# Serial.net
KiCad netlist of a schematic drawn in Altium Designer
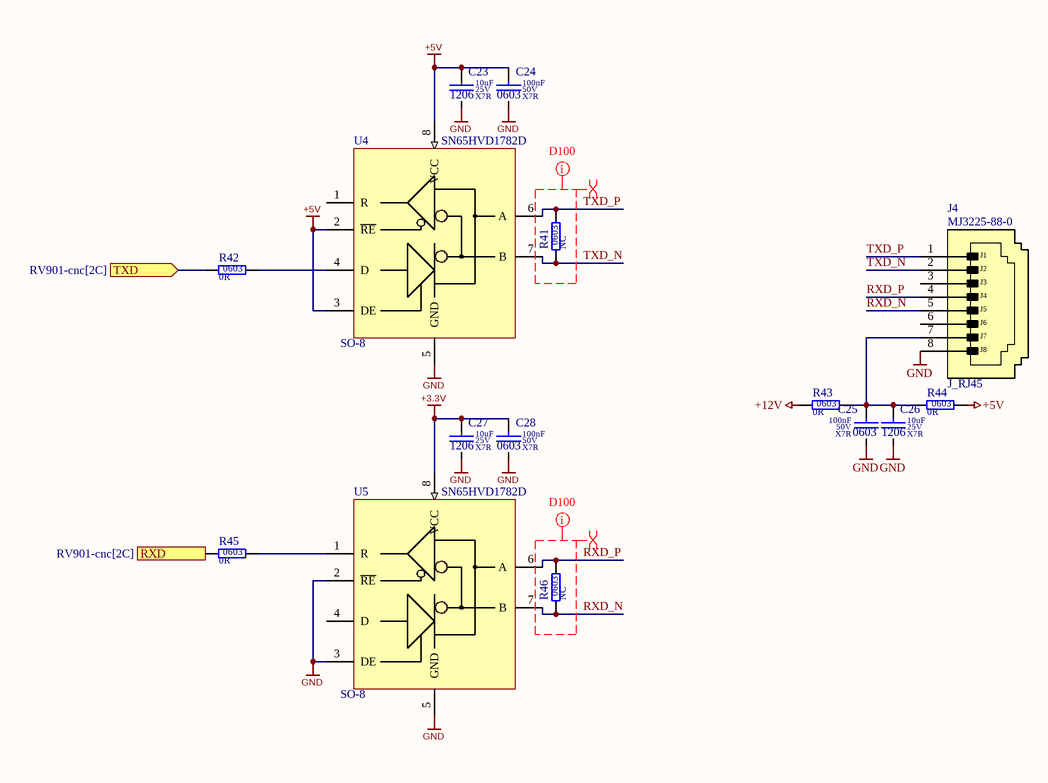
[diagram p0: Serial.SchDoc]

(export (version "E")
  (design (tool "Eeschema 10.0.6"))
  (components
    (comp (ref "C23")
      (value "10uF")
      (footprint "C_1206_3216")
      (description "Capacitor")
      (fields
        (field (name "DIELECTRIC") "X7R")
        (field (name "VOLTAGE") "25V")
        (field (name "SCH_FOOTPRINT") "1206")
        (field (name "PART NUMBER") "C_10uF_25V_X7R_1206_10")
        (field (name "MANUFACTURER") "Samsung")
      )
      (libsource (lib "Library") (part "C"))
    )
    (comp (ref "C24")
      (value "100nF")
      (footprint "C_0603_1608")
      (description "Capacitor")
      (fields
        (field (name "DIELECTRIC") "X7R")
        (field (name "VOLTAGE") "50V")
        (field (name "SCH_FOOTPRINT") "0603")
        (field (name "PART NUMBER") "C_100nF_50V_X7R_0603_5")
        (field (name "MANUFACTURER") "Samsung")
      )
      (libsource (lib "Library") (part "C"))
    )
    (comp (ref "C25")
      (value "100nF")
      (footprint "C_0603_1608")
      (description "Capacitor")
      (fields
        (field (name "DIELECTRIC") "X7R")
        (field (name "VOLTAGE") "50V")
        (field (name "SCH_FOOTPRINT") "0603")
        (field (name "PART NUMBER") "C_100nF_50V_X7R_0603_5")
        (field (name "MANUFACTURER") "Samsung")
      )
      (libsource (lib "Library") (part "C"))
    )
    (comp (ref "C26")
      (value "10uF")
      (footprint "C_1206_3216")
      (description "Capacitor")
      (fields
        (field (name "DIELECTRIC") "X7R")
        (field (name "VOLTAGE") "25V")
        (field (name "SCH_FOOTPRINT") "1206")
        (field (name "PART NUMBER") "C_10uF_25V_X7R_1206_10")
        (field (name "MANUFACTURER") "Samsung")
      )
      (libsource (lib "Library") (part "C"))
    )
    (comp (ref "C27")
      (value "10uF")
      (footprint "C_1206_3216")
      (description "Capacitor")
      (fields
        (field (name "DIELECTRIC") "X7R")
        (field (name "VOLTAGE") "25V")
        (field (name "SCH_FOOTPRINT") "1206")
        (field (name "PART NUMBER") "C_10uF_25V_X7R_1206_10")
        (field (name "MANUFACTURER") "Samsung")
      )
      (libsource (lib "Library") (part "C"))
    )
    (comp (ref "C28")
      (value "100nF")
      (footprint "C_0603_1608")
      (description "Capacitor")
      (fields
        (field (name "DIELECTRIC") "X7R")
        (field (name "VOLTAGE") "50V")
        (field (name "SCH_FOOTPRINT") "0603")
        (field (name "PART NUMBER") "C_100nF_50V_X7R_0603_5")
        (field (name "MANUFACTURER") "Samsung")
      )
      (libsource (lib "Library") (part "C"))
    )
    (comp (ref "J4")
      (value "MJ3225-88-0")
      (footprint "J_RJ45_MJ3225-88-0")
      (fields
        (field (name "SCH_FOOTPRINT") "J_RJ45")
        (field (name "PART NUMBER") "J_RJ45_MJ3225-88-0")
        (field (name "MANUFACTURER") "Global Connector Technology")
        (field (name "Comment") "Modular Connector, Modular Jack, 1 x 1 (Port), 8P8C, Cat3")
      )
      (libsource (lib "Library") (part "J_RJ45"))
    )
    (comp (ref "R41")
      (value "NC")
      (footprint "R_NC_0603_1608")
      (fields
        (field (name "SCH_FOOTPRINT") "0603")
        (field (name "PART NUMBER") "R_GENERIC_0603")
        (field (name "Comment") "Resistor")
      )
      (libsource (lib "Library") (part "R"))
    )
    (comp (ref "R42")
      (value "0R")
      (footprint "R_0603_1608")
      (fields
        (field (name "SCH_FOOTPRINT") "0603")
        (field (name "PART NUMBER") "R_0R_0603_1")
        (field (name "VOLTAGE") "75V")
        (field (name "POWER") "100mW")
      )
      (libsource (lib "Library") (part "R"))
    )
    (comp (ref "R43")
      (value "0R")
      (footprint "R_0603_1608")
      (fields
        (field (name "SCH_FOOTPRINT") "0603")
        (field (name "PART NUMBER") "R_0R_0603_1")
        (field (name "VOLTAGE") "75V")
        (field (name "POWER") "100mW")
      )
      (libsource (lib "Library") (part "R"))
    )
    (comp (ref "R44")
      (value "0R")
      (footprint "R_0603_1608")
      (fields
        (field (name "SCH_FOOTPRINT") "0603")
        (field (name "PART NUMBER") "R_0R_0603_1")
        (field (name "VOLTAGE") "75V")
        (field (name "POWER") "100mW")
      )
      (libsource (lib "Library") (part "R"))
    )
    (comp (ref "R45")
      (value "0R")
      (footprint "R_0603_1608")
      (fields
        (field (name "SCH_FOOTPRINT") "0603")
        (field (name "PART NUMBER") "R_0R_0603_1")
        (field (name "VOLTAGE") "75V")
        (field (name "POWER") "100mW")
      )
      (libsource (lib "Library") (part "R"))
    )
    (comp (ref "R46")
      (value "NC")
      (footprint "R_NC_0603_1608")
      (fields
        (field (name "SCH_FOOTPRINT") "0603")
        (field (name "PART NUMBER") "R_GENERIC_0603")
        (field (name "Comment") "Resistor")
      )
      (libsource (lib "Library") (part "R"))
    )
    (comp (ref "U4")
      (value "SN65HVD1782D")
      (footprint "SOP8_SO8_SOIC8_4X5X18")
      (description "Fault-Protected  RS-485  Transceivers  With 3.3-V to 5-V Operation")
      (fields
        (field (name "SCH_FOOTPRINT") "SO-8")
        (field (name "PART NUMBER") "U_SN65HVD1782DR")
        (field (name "MANUFACTURER") "Texas Instruments")
      )
      (libsource (lib "Library") (part "U_RS485_HD_GENERIC"))
    )
    (comp (ref "U5")
      (value "SN65HVD1782D")
      (footprint "SOP8_SO8_SOIC8_4X5X18")
      (description "Fault-Protected  RS-485  Transceivers  With 3.3-V to 5-V Operation")
      (fields
        (field (name "SCH_FOOTPRINT") "SO-8")
        (field (name "PART NUMBER") "U_SN65HVD1782DR")
        (field (name "MANUFACTURER") "Texas Instruments")
      )
      (libsource (lib "Library") (part "U_RS485_HD_GENERIC"))
    )
  )
  (nets
    (net (code "1") (name "+3.3V") (class "Default")
      (node (ref "C27") (pin "1") (pinfunction "1_1") (pintype "passive"))
      (node (ref "C28") (pin "1") (pinfunction "1_1") (pintype "passive"))
      (node (ref "U5") (pin "8") (pinfunction "VCC_8") (pintype "input"))
    )
    (net (code "2") (name "+5V") (class "Default")
      (node (ref "C23") (pin "1") (pinfunction "1_1") (pintype "passive"))
      (node (ref "C24") (pin "1") (pinfunction "1_1") (pintype "passive"))
      (node (ref "R44") (pin "2") (pinfunction "2_2") (pintype "passive"))
      (node (ref "U4") (pin "2") (pinfunction "~{RE}_2") (pintype "passive"))
      (node (ref "U4") (pin "3") (pinfunction "DE_3") (pintype "passive"))
      (node (ref "U4") (pin "8") (pinfunction "VCC_8") (pintype "input"))
    )
    (net (code "3") (name "+12V") (class "Default")
      (node (ref "R43") (pin "1") (pinfunction "1_1") (pintype "passive"))
    )
    (net (code "4") (name "/RXD") (class "Default")
      (node (ref "R45") (pin "1") (pinfunction "1_1") (pintype "passive"))
    )
    (net (code "5") (name "/RXD_N") (class "Default")
      (node (ref "J4") (pin "5") (pintype "passive"))
      (node (ref "R46") (pin "1") (pinfunction "1_1") (pintype "passive"))
      (node (ref "U5") (pin "7") (pinfunction "B_7") (pintype "passive"))
    )
    (net (code "6") (name "/RXD_P") (class "Default")
      (node (ref "J4") (pin "4") (pintype "passive"))
      (node (ref "R46") (pin "2") (pinfunction "2_2") (pintype "passive"))
      (node (ref "U5") (pin "6") (pinfunction "A_6") (pintype "passive"))
    )
    (net (code "7") (name "/TXD") (class "Default")
      (node (ref "R42") (pin "1") (pinfunction "1_1") (pintype "passive"))
    )
    (net (code "8") (name "/TXD_N") (class "Default")
      (node (ref "J4") (pin "2") (pintype "passive"))
      (node (ref "R41") (pin "1") (pinfunction "1_1") (pintype "passive"))
      (node (ref "U4") (pin "7") (pinfunction "B_7") (pintype "passive"))
    )
    (net (code "9") (name "/TXD_P") (class "Default")
      (node (ref "J4") (pin "1") (pintype "passive"))
      (node (ref "R41") (pin "2") (pinfunction "2_2") (pintype "passive"))
      (node (ref "U4") (pin "6") (pinfunction "A_6") (pintype "passive"))
    )
    (net (code "10") (name "GND") (class "Default")
      (node (ref "C23") (pin "2") (pinfunction "2_2") (pintype "passive"))
      (node (ref "C24") (pin "2") (pinfunction "2_2") (pintype "passive"))
      (node (ref "C25") (pin "2") (pinfunction "2_2") (pintype "passive"))
      (node (ref "C26") (pin "2") (pinfunction "2_2") (pintype "passive"))
      (node (ref "C27") (pin "2") (pinfunction "2_2") (pintype "passive"))
      (node (ref "C28") (pin "2") (pinfunction "2_2") (pintype "passive"))
      (node (ref "J4") (pin "8") (pintype "passive"))
      (node (ref "U4") (pin "5") (pinfunction "GND_5") (pintype "power_in"))
      (node (ref "U5") (pin "2") (pinfunction "~{RE}_2") (pintype "passive"))
      (node (ref "U5") (pin "3") (pinfunction "DE_3") (pintype "passive"))
      (node (ref "U5") (pin "5") (pinfunction "GND_5") (pintype "power_in"))
    )
    (net (code "11") (name "Net-(C25-Pad1)") (class "Default")
      (node (ref "C25") (pin "1") (pinfunction "1_1") (pintype "passive"))
      (node (ref "C26") (pin "1") (pinfunction "1_1") (pintype "passive"))
      (node (ref "J4") (pin "7") (pintype "passive"))
      (node (ref "R43") (pin "2") (pinfunction "2_2") (pintype "passive"))
      (node (ref "R44") (pin "1") (pinfunction "1_1") (pintype "passive"))
    )
    (net (code "12") (name "Net-(U4-D)") (class "Default")
      (node (ref "R42") (pin "2") (pinfunction "2_2") (pintype "passive"))
      (node (ref "U4") (pin "4") (pinfunction "D_4") (pintype "passive"))
    )
    (net (code "13") (name "Net-(U5-R)") (class "Default")
      (node (ref "R45") (pin "2") (pinfunction "2_2") (pintype "passive"))
      (node (ref "U5") (pin "1") (pinfunction "R_1") (pintype "passive"))
    )
    (net (code "14") (name "unconnected-(J4-Pad3)") (class "Default")
      (node (ref "J4") (pin "3") (pintype "passive"))
    )
    (net (code "15") (name "unconnected-(J4-Pad6)") (class "Default")
      (node (ref "J4") (pin "6") (pintype "passive"))
    )
    (net (code "16") (name "unconnected-(U4-R-Pad1)") (class "Default")
      (node (ref "U4") (pin "1") (pinfunction "R_1") (pintype "passive"))
    )
    (net (code "17") (name "unconnected-(U5-D-Pad4)") (class "Default")
      (node (ref "U5") (pin "4") (pinfunction "D_4") (pintype "passive"))
    )
  )
)
